# TDA_2050_-_32W_DON.net
KiCad netlist of a schematic drawn in Altium Designer
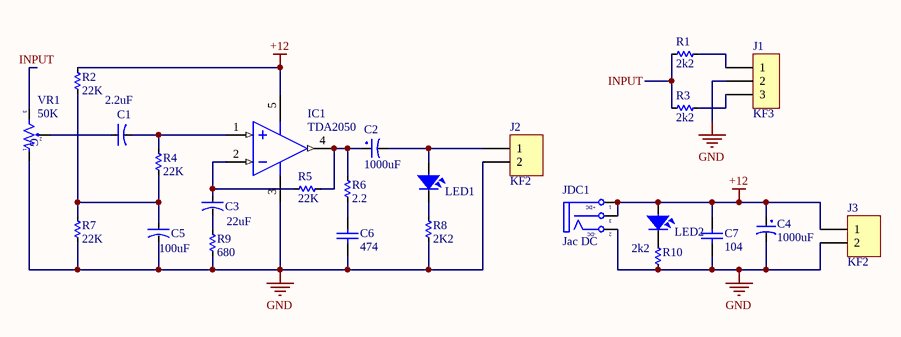
[diagram p0: TDA 2050 - 32W DON.SchDoc]

(export (version "E")
  (design (tool "Eeschema 10.0.6"))
  (components
    (comp (ref "C1")
      (value "2.2uF")
      (footprint "CA-ALU-5")
      (description "Capacitor (Semiconductor SIM Model)")
      (fields (field (name "PUBLISHER") "Altium Limited"))
      (libsource (lib "LIBRARY") (part "CN-ALU-DIP"))
    )
    (comp (ref "C2")
      (value "1000uF")
      (footprint "tu hoa 13mm")
      (description "Cắm")
      (libsource (lib "") (part "Tu Hoa 1000uF 50V 13x26_1"))
    )
    (comp (ref "C3")
      (value "22uF")
      (footprint "CA-ALU-5")
      (description "Capacitor (Semiconductor SIM Model)")
      (fields (field (name "PUBLISHER") "Altium Limited"))
      (libsource (lib "LIBRARY") (part "CN-ALU-DIP"))
    )
    (comp (ref "C4")
      (value "1000uF")
      (footprint "tu hoa 13mm")
      (description "Cắm")
      (libsource (lib "Tu dien") (part "Tu Hoa 1000uF 50V 13x26"))
    )
    (comp (ref "C5")
      (value "100uF")
      (footprint "CA-ALU-5")
      (description "Capacitor (Semiconductor SIM Model)")
      (fields (field (name "PUBLISHER") "Altium Limited"))
      (libsource (lib "LIBRARY") (part "CN-ALU-DIP"))
    )
    (comp (ref "C6")
      (value "474")
      (footprint "tu gom")
      (description "Cắm")
      (libsource (lib "Tu dien") (part "Tu gom 104 50V"))
    )
    (comp (ref "C7")
      (value "104")
      (footprint "tu gom")
      (description "Cắm")
      (libsource (lib "Tu dien") (part "Tu gom 104 50V"))
    )
    (comp (ref "IC1") (value "TDA2050") (footprint "DIP5") (libsource (lib "LIBRARY") (part "TDA2050")))
    (comp (ref "J1")
      (value "KF3")
      (footprint "KF3-5.08")
      (fields
        (field (name "MANUFACTURER") "Würth Elektronik eiSos GmbH")
        (field (name "PARTNO") "691103110003")
        (field (name "CREATED BY") "Karrer Zheng")
      )
      (libsource (lib "LIBRARY") (part "KF3"))
    )
    (comp (ref "J2")
      (value "KF2")
      (footprint "KF2-5.08")
      (fields
        (field (name "MANUFACTURER") "Würth Elektronik eiSos GmbH")
        (field (name "PARTNO") "691103110002")
        (field (name "CREATED BY") "Karrer Zheng")
      )
      (libsource (lib "LIBRARY") (part "KF2"))
    )
    (comp (ref "J3")
      (value "KF2")
      (footprint "KF2-5.08")
      (fields
        (field (name "MANUFACTURER") "Würth Elektronik eiSos GmbH")
        (field (name "PARTNO") "691103110002")
        (field (name "CREATED BY") "Karrer Zheng")
      )
      (libsource (lib "LIBRARY") (part "KF2"))
    )
    (comp (ref "JDC1")
      (value "Jac DC")
      (footprint "DC0")
      (description "Jac DC input")
      (libsource (lib "LIBRARY") (part "DCIN"))
    )
    (comp (ref "LED1")
      (value "LED")
      (footprint "LED-5-RED")
      (description "LED Single colour Green and Red")
      (libsource (lib "LIBRARY") (part "LED"))
    )
    (comp (ref "LED2")
      (value "LED")
      (footprint "LED-5-BLUE")
      (description "LED Single colour Green and Red")
      (libsource (lib "LIBRARY") (part "LED"))
    )
    (comp (ref "R1")
      (value "2k2")
      (footprint "RES-1/4W-SMALL")
      (description "Res")
      (fields
        (field (name "MANUFACTURER") "Generic Components")
        (field (name "PUBLISHER") "Altium Hobart Technology Centre")
      )
      (libsource (lib "LIBRARY") (part "Res"))
    )
    (comp (ref "R2")
      (value "22K")
      (footprint "RES-1/4W-SMALL")
      (description "Res")
      (fields
        (field (name "MANUFACTURER") "Generic Components")
        (field (name "PUBLISHER") "Altium Hobart Technology Centre")
      )
      (libsource (lib "LIBRARY") (part "Res"))
    )
    (comp (ref "R3")
      (value "2k2")
      (footprint "RES-1/4W-SMALL")
      (description "Res")
      (fields
        (field (name "MANUFACTURER") "Generic Components")
        (field (name "PUBLISHER") "Altium Hobart Technology Centre")
      )
      (libsource (lib "LIBRARY") (part "Res"))
    )
    (comp (ref "R4")
      (value "22K")
      (footprint "RES-1/4W-SMALL")
      (description "Res")
      (fields
        (field (name "MANUFACTURER") "Generic Components")
        (field (name "PUBLISHER") "Altium Hobart Technology Centre")
      )
      (libsource (lib "LIBRARY") (part "Res"))
    )
    (comp (ref "R5")
      (value "22K")
      (footprint "RES-1/4W-SMALL")
      (description "Res")
      (fields
        (field (name "MANUFACTURER") "Generic Components")
        (field (name "PUBLISHER") "Altium Hobart Technology Centre")
      )
      (libsource (lib "LIBRARY") (part "Res"))
    )
    (comp (ref "R6")
      (value "2.2")
      (footprint "RES-1/4W-SMALL")
      (description "Res")
      (fields
        (field (name "MANUFACTURER") "Generic Components")
        (field (name "PUBLISHER") "Altium Hobart Technology Centre")
      )
      (libsource (lib "LIBRARY") (part "Res"))
    )
    (comp (ref "R7")
      (value "22K")
      (footprint "RES-1/4W-SMALL")
      (description "Res")
      (fields
        (field (name "MANUFACTURER") "Generic Components")
        (field (name "PUBLISHER") "Altium Hobart Technology Centre")
      )
      (libsource (lib "LIBRARY") (part "Res"))
    )
    (comp (ref "R8")
      (value "2K2")
      (footprint "RES-1/4W-SMALL")
      (description "Res")
      (fields
        (field (name "MANUFACTURER") "Generic Components")
        (field (name "PUBLISHER") "Altium Hobart Technology Centre")
      )
      (libsource (lib "LIBRARY") (part "Res"))
    )
    (comp (ref "R9")
      (value "680")
      (footprint "RES-1/4W-SMALL")
      (description "Res")
      (fields
        (field (name "MANUFACTURER") "Generic Components")
        (field (name "PUBLISHER") "Altium Hobart Technology Centre")
      )
      (libsource (lib "LIBRARY") (part "Res"))
    )
    (comp (ref "R10")
      (value "2k2")
      (footprint "RES-1/4W-SMALL")
      (description "Res")
      (fields
        (field (name "MANUFACTURER") "Generic Components")
        (field (name "PUBLISHER") "Altium Hobart Technology Centre")
      )
      (libsource (lib "LIBRARY") (part "Res"))
    )
    (comp (ref "VR1")
      (value "50K")
      (footprint "VR-S1")
      (description "Var Resistor")
      (libsource (lib "LIBRARY") (part "VR-S"))
    )
  )
  (nets
    (net (code "1") (name "+12") (class "Default")
      (node (ref "C4") (pin "1") (pinfunction "1_1") (pintype "passive"))
      (node (ref "C7") (pin "1") (pinfunction "1_1") (pintype "passive"))
      (node (ref "IC1") (pin "5") (pinfunction "V+_5") (pintype "power_in"))
      (node (ref "J3") (pin "1") (pinfunction "1_1") (pintype "passive"))
      (node (ref "JDC1") (pin "1") (pinfunction "T_1") (pintype "passive"))
      (node (ref "JDC1") (pin "3") (pinfunction "S_3") (pintype "power_in"))
      (node (ref "LED2") (pin "1") (pinfunction "1_1") (pintype "passive"))
      (node (ref "R2") (pin "1") (pinfunction "1_1") (pintype "passive"))
    )
    (net (code "2") (name "/INPUT") (class "Default")
      (node (ref "R1") (pin "1") (pinfunction "1_1") (pintype "passive"))
      (node (ref "R3") (pin "2") (pinfunction "2_2") (pintype "passive"))
      (node (ref "VR1") (pin "3") (pinfunction "3_3") (pintype "passive"))
    )
    (net (code "3") (name "GND") (class "Default")
      (node (ref "C4") (pin "2") (pinfunction "2_2") (pintype "passive"))
      (node (ref "C5") (pin "2") (pinfunction "2_2") (pintype "passive"))
      (node (ref "C6") (pin "2") (pinfunction "2_2") (pintype "passive"))
      (node (ref "C7") (pin "2") (pinfunction "2_2") (pintype "passive"))
      (node (ref "IC1") (pin "3") (pinfunction "V-_3") (pintype "power_in"))
      (node (ref "J1") (pin "2") (pinfunction "2_2") (pintype "passive"))
      (node (ref "J2") (pin "2") (pinfunction "2_2") (pintype "passive"))
      (node (ref "J3") (pin "2") (pinfunction "2_2") (pintype "passive"))
      (node (ref "JDC1") (pin "2") (pinfunction "TN_2") (pintype "passive"))
      (node (ref "R10") (pin "2") (pinfunction "2_2") (pintype "passive"))
      (node (ref "R7") (pin "2") (pinfunction "2_2") (pintype "passive"))
      (node (ref "R8") (pin "2") (pinfunction "2_2") (pintype "passive"))
      (node (ref "R9") (pin "2") (pinfunction "2_2") (pintype "passive"))
      (node (ref "VR1") (pin "1") (pinfunction "1_1") (pintype "passive"))
    )
    (net (code "4") (name "Net-(C1-Pad1)") (class "Default")
      (node (ref "C1") (pin "1") (pinfunction "1_1") (pintype "passive"))
      (node (ref "VR1") (pin "2") (pinfunction "2_2") (pintype "passive"))
    )
    (net (code "5") (name "Net-(C2-Pad2)") (class "Default")
      (node (ref "C2") (pin "2") (pinfunction "2_2") (pintype "passive"))
      (node (ref "J2") (pin "1") (pinfunction "1_1") (pintype "passive"))
      (node (ref "LED1") (pin "1") (pinfunction "1_1") (pintype "passive"))
    )
    (net (code "6") (name "Net-(C3-Pad2)") (class "Default")
      (node (ref "C3") (pin "2") (pinfunction "2_2") (pintype "passive"))
      (node (ref "R9") (pin "1") (pinfunction "1_1") (pintype "passive"))
    )
    (net (code "7") (name "Net-(C5-Pad1)") (class "Default")
      (node (ref "C5") (pin "1") (pinfunction "1_1") (pintype "passive"))
      (node (ref "R2") (pin "2") (pinfunction "2_2") (pintype "passive"))
      (node (ref "R4") (pin "2") (pinfunction "2_2") (pintype "passive"))
      (node (ref "R7") (pin "1") (pinfunction "1_1") (pintype "passive"))
    )
    (net (code "8") (name "Net-(C6-Pad1)") (class "Default")
      (node (ref "C6") (pin "1") (pinfunction "1_1") (pintype "passive"))
      (node (ref "R6") (pin "2") (pinfunction "2_2") (pintype "passive"))
    )
    (net (code "9") (name "Net-(IC1-IN+)") (class "Default")
      (node (ref "C1") (pin "2") (pinfunction "2_2") (pintype "passive"))
      (node (ref "IC1") (pin "1") (pinfunction "IN+_1") (pintype "input"))
      (node (ref "R4") (pin "1") (pinfunction "1_1") (pintype "passive"))
    )
    (net (code "10") (name "Net-(IC1-IN-)") (class "Default")
      (node (ref "C3") (pin "1") (pinfunction "1_1") (pintype "passive"))
      (node (ref "IC1") (pin "2") (pinfunction "IN-_2") (pintype "input"))
      (node (ref "R5") (pin "1") (pinfunction "1_1") (pintype "passive"))
    )
    (net (code "11") (name "Net-(IC1-OUT)") (class "Default")
      (node (ref "C2") (pin "1") (pinfunction "1_1") (pintype "passive"))
      (node (ref "IC1") (pin "4") (pinfunction "OUT_4") (pintype "output"))
      (node (ref "R5") (pin "2") (pinfunction "2_2") (pintype "passive"))
      (node (ref "R6") (pin "1") (pinfunction "1_1") (pintype "passive"))
    )
    (net (code "12") (name "Net-(J1-Pad1)") (class "Default")
      (node (ref "J1") (pin "1") (pinfunction "1_1") (pintype "passive"))
      (node (ref "R1") (pin "2") (pinfunction "2_2") (pintype "passive"))
    )
    (net (code "13") (name "Net-(J1-Pad3)") (class "Default")
      (node (ref "J1") (pin "3") (pinfunction "3_3") (pintype "passive"))
      (node (ref "R3") (pin "1") (pinfunction "1_1") (pintype "passive"))
    )
    (net (code "14") (name "Net-(LED1-Pad2)") (class "Default")
      (node (ref "LED1") (pin "2") (pinfunction "2_2") (pintype "passive"))
      (node (ref "R8") (pin "1") (pinfunction "1_1") (pintype "passive"))
    )
    (net (code "15") (name "Net-(LED2-Pad2)") (class "Default")
      (node (ref "LED2") (pin "2") (pinfunction "2_2") (pintype "passive"))
      (node (ref "R10") (pin "1") (pinfunction "1_1") (pintype "passive"))
    )
  )
)
